# dasblinkenhat-controller-mk-3_0.net
KiCad netlist of a schematic drawn in EAGLE
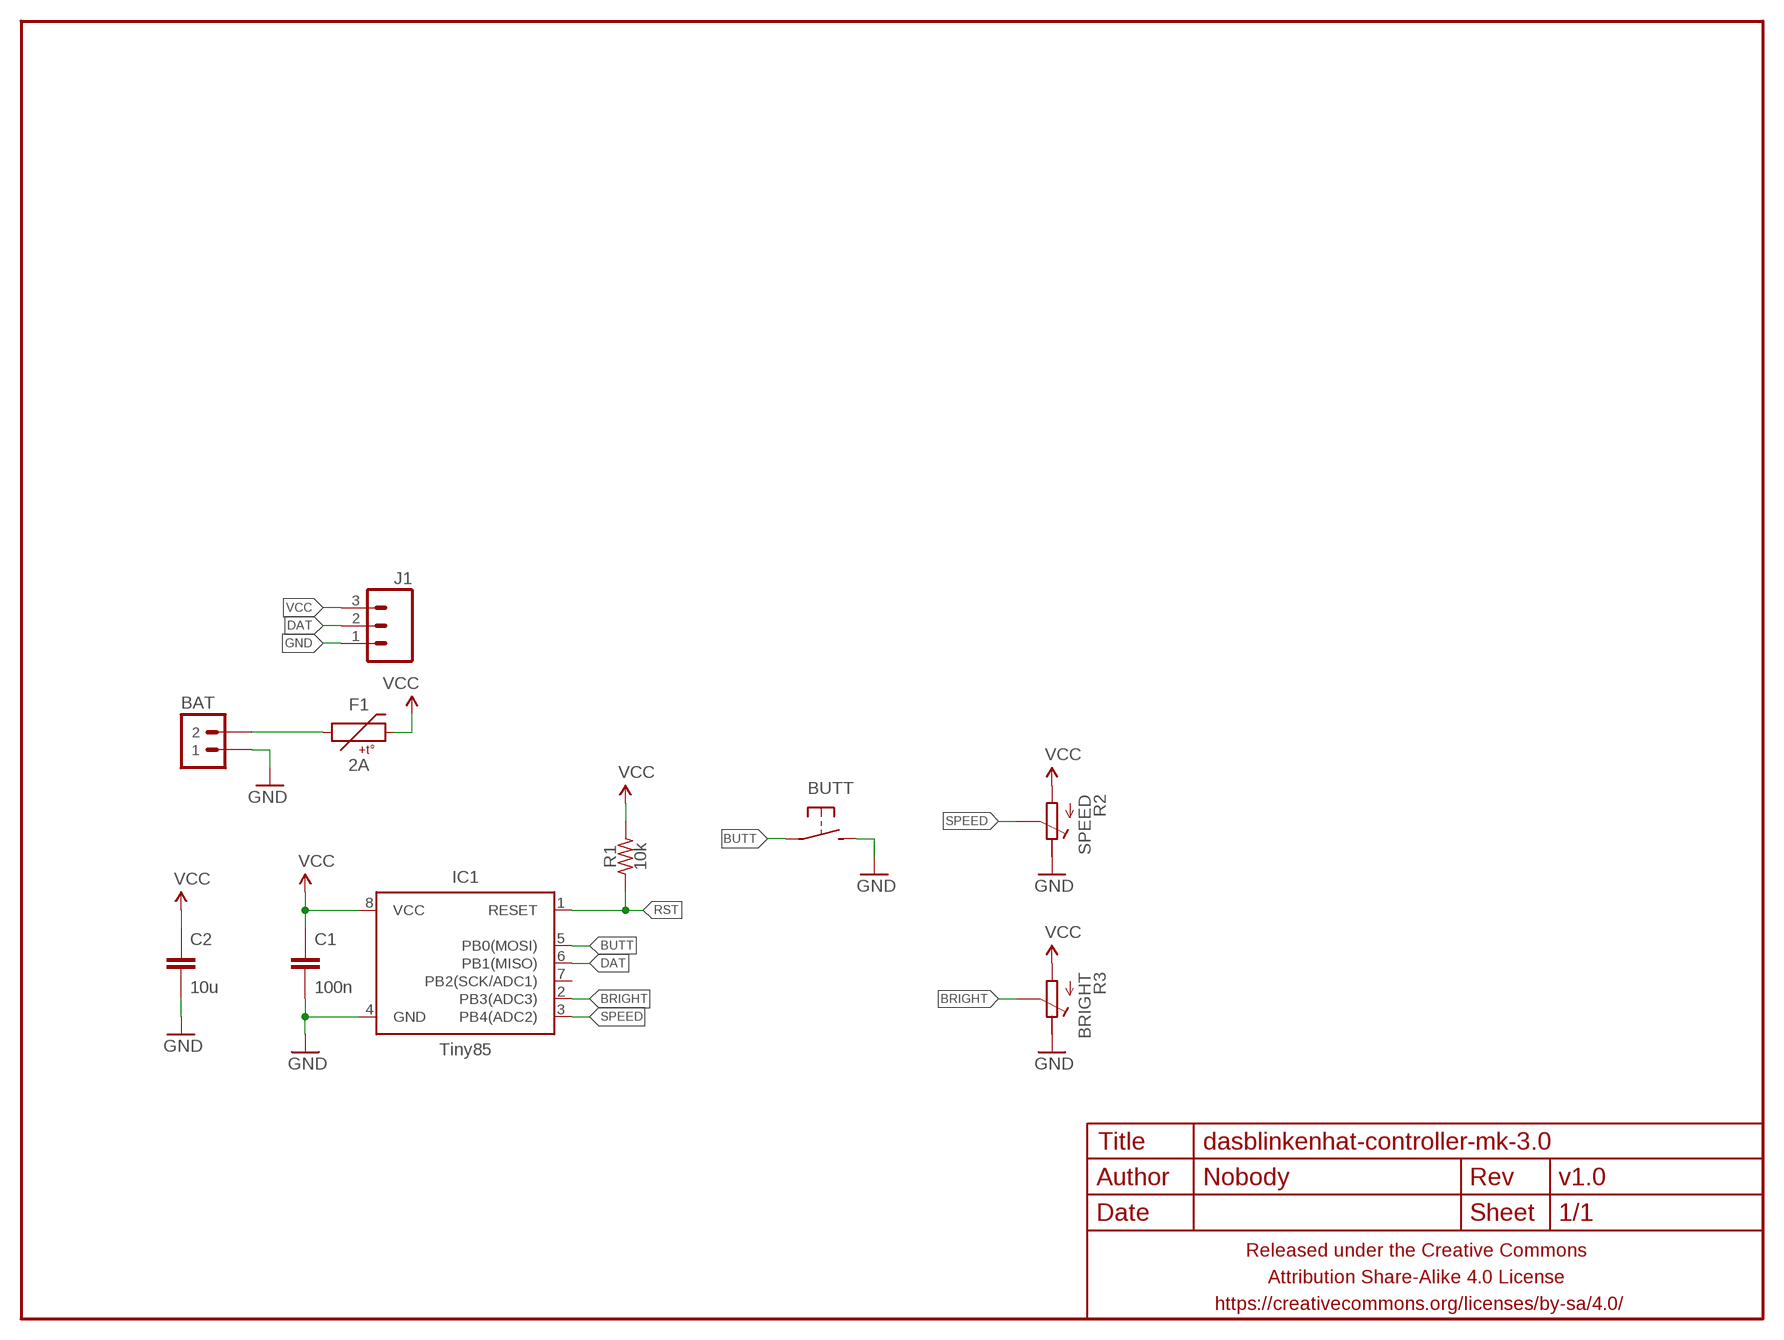
[diagram p0: schematic, sheet 1]

(export (version "E")
  (design (tool "Eeschema 10.0.6"))
  (components
    (comp (ref "BAT")
      (value "M02JST-PTH-RA-R+")
      (footprint "eagle-import:JST-2-PH-RA-PTH-R+")
      (libsource (lib "eagle-import") (part "M02JST-PTH-RA-R+"))
    )
    (comp (ref "BUTT")
      (value "DTS-6MM")
      (footprint "eagle-import:DTSM-6")
      (libsource (lib "eagle-import") (part "SPST-NO-TACT6MM-SMD"))
    )
    (comp (ref "C1")
      (value "100n")
      (footprint "eagle-import:C0603")
      (libsource (lib "eagle-import") (part "CAPACITOR-CERAMICC0603"))
    )
    (comp (ref "C2")
      (value "10u")
      (footprint "eagle-import:C1206")
      (libsource (lib "eagle-import") (part "CAPACITOR-CERAMICC1206"))
    )
    (comp (ref "F1")
      (value "2A")
      (footprint "eagle-import:PTC-1206")
      (libsource (lib "eagle-import") (part "PTCSMD"))
    )
    (comp (ref "FRAME1")
      (value "FRAME-LETTERNO_PACKAGE")
      (footprint "eagle-import:DUMMY")
      (fields (field (name "VERSION") "v1.0") (field (name "DESIGNER") "Nobody"))
      (libsource (lib "eagle-import") (part "FRAME-LETTERNO_PACKAGE"))
    )
    (comp (ref "IC1")
      (value "Tiny85")
      (footprint "eagle-import:SO08-EIAJ")
      (libsource (lib "eagle-import") (part "ATTINY45TINY85-20-SOICW"))
    )
    (comp (ref "J1")
      (value "M03JST-XH-RA-PTH")
      (footprint "eagle-import:JST-3-XH-RA-PTH")
      (libsource (lib "eagle-import") (part "M03JST-XH-RA-PTH"))
    )
    (comp (ref "R1")
      (value "10k")
      (footprint "eagle-import:R0603")
      (libsource (lib "eagle-import") (part "RESISTORR0603"))
    )
    (comp (ref "R2")
      (value "SPEED")
      (footprint "eagle-import:EVM3Y")
      (libsource (lib "eagle-import") (part "POTENTIOMETEREVM3Y"))
    )
    (comp (ref "R3")
      (value "BRIGHT")
      (footprint "eagle-import:EVM3Y")
      (libsource (lib "eagle-import") (part "POTENTIOMETEREVM3Y"))
    )
  )
  (nets
    (net (code "1") (name "BRIGHT") (class "Default")
      (node (ref "IC1") (pin "2") (pinfunction "PB3(ADC3)_2") (pintype "bidirectional"))
      (node (ref "R3") (pin "S") (pinfunction "S_S") (pintype "passive"))
    )
    (net (code "2") (name "BUTT") (class "Default")
      (node (ref "BUTT") (pin "1") (pinfunction "1_1") (pintype "passive"))
      (node (ref "BUTT") (pin "2") (pinfunction "1_2") (pintype "passive"))
      (node (ref "IC1") (pin "5") (pinfunction "PB0(MOSI)_5") (pintype "bidirectional"))
    )
    (net (code "3") (name "DAT") (class "Default")
      (node (ref "IC1") (pin "6") (pinfunction "PB1(MISO)_6") (pintype "bidirectional"))
      (node (ref "J1") (pin "2") (pinfunction "2_2") (pintype "passive"))
    )
    (net (code "4") (name "GND") (class "Default")
      (node (ref "BAT") (pin "1") (pinfunction "1_1") (pintype "passive"))
      (node (ref "BUTT") (pin "3") (pinfunction "2_3") (pintype "passive"))
      (node (ref "BUTT") (pin "4") (pinfunction "2_4") (pintype "passive"))
      (node (ref "C1") (pin "2") (pinfunction "2_2") (pintype "passive"))
      (node (ref "C2") (pin "2") (pinfunction "2_2") (pintype "passive"))
      (node (ref "IC1") (pin "4") (pinfunction "GND_4") (pintype "bidirectional"))
      (node (ref "J1") (pin "1") (pinfunction "1_1") (pintype "passive"))
      (node (ref "R2") (pin "E") (pinfunction "E_E") (pintype "passive"))
      (node (ref "R3") (pin "E") (pinfunction "E_E") (pintype "passive"))
    )
    (net (code "5") (name "Net-(BAT-Pad2)") (class "Default")
      (node (ref "BAT") (pin "2") (pinfunction "2_2") (pintype "passive"))
      (node (ref "F1") (pin "1") (pinfunction "1_1") (pintype "passive"))
    )
    (net (code "6") (name "RST") (class "Default")
      (node (ref "IC1") (pin "1") (pinfunction "RESET_1") (pintype "bidirectional"))
      (node (ref "R1") (pin "1") (pinfunction "1_1") (pintype "passive"))
    )
    (net (code "7") (name "SPEED") (class "Default")
      (node (ref "IC1") (pin "3") (pinfunction "PB4(ADC2)_3") (pintype "bidirectional"))
      (node (ref "R2") (pin "S") (pinfunction "S_S") (pintype "passive"))
    )
    (net (code "8") (name "VCC") (class "Default")
      (node (ref "C1") (pin "1") (pinfunction "1_1") (pintype "passive"))
      (node (ref "C2") (pin "1") (pinfunction "1_1") (pintype "passive"))
      (node (ref "F1") (pin "2") (pinfunction "2_2") (pintype "passive"))
      (node (ref "IC1") (pin "8") (pinfunction "VCC_8") (pintype "bidirectional"))
      (node (ref "J1") (pin "3") (pinfunction "3_3") (pintype "passive"))
      (node (ref "R1") (pin "2") (pinfunction "2_2") (pintype "passive"))
      (node (ref "R2") (pin "A") (pinfunction "A_A") (pintype "passive"))
      (node (ref "R3") (pin "A") (pinfunction "A_A") (pintype "passive"))
    )
    (net (code "9") (name "unconnected-(IC1-PB2(SCK{slash}ADC1)-Pad7)") (class "Default")
      (node (ref "IC1") (pin "7") (pinfunction "PB2(SCK/ADC1)_7") (pintype "bidirectional"))
    )
  )
)
